# YUSynth-LFO-ioboard.net
KiCad netlist of a schematic drawn in EAGLE
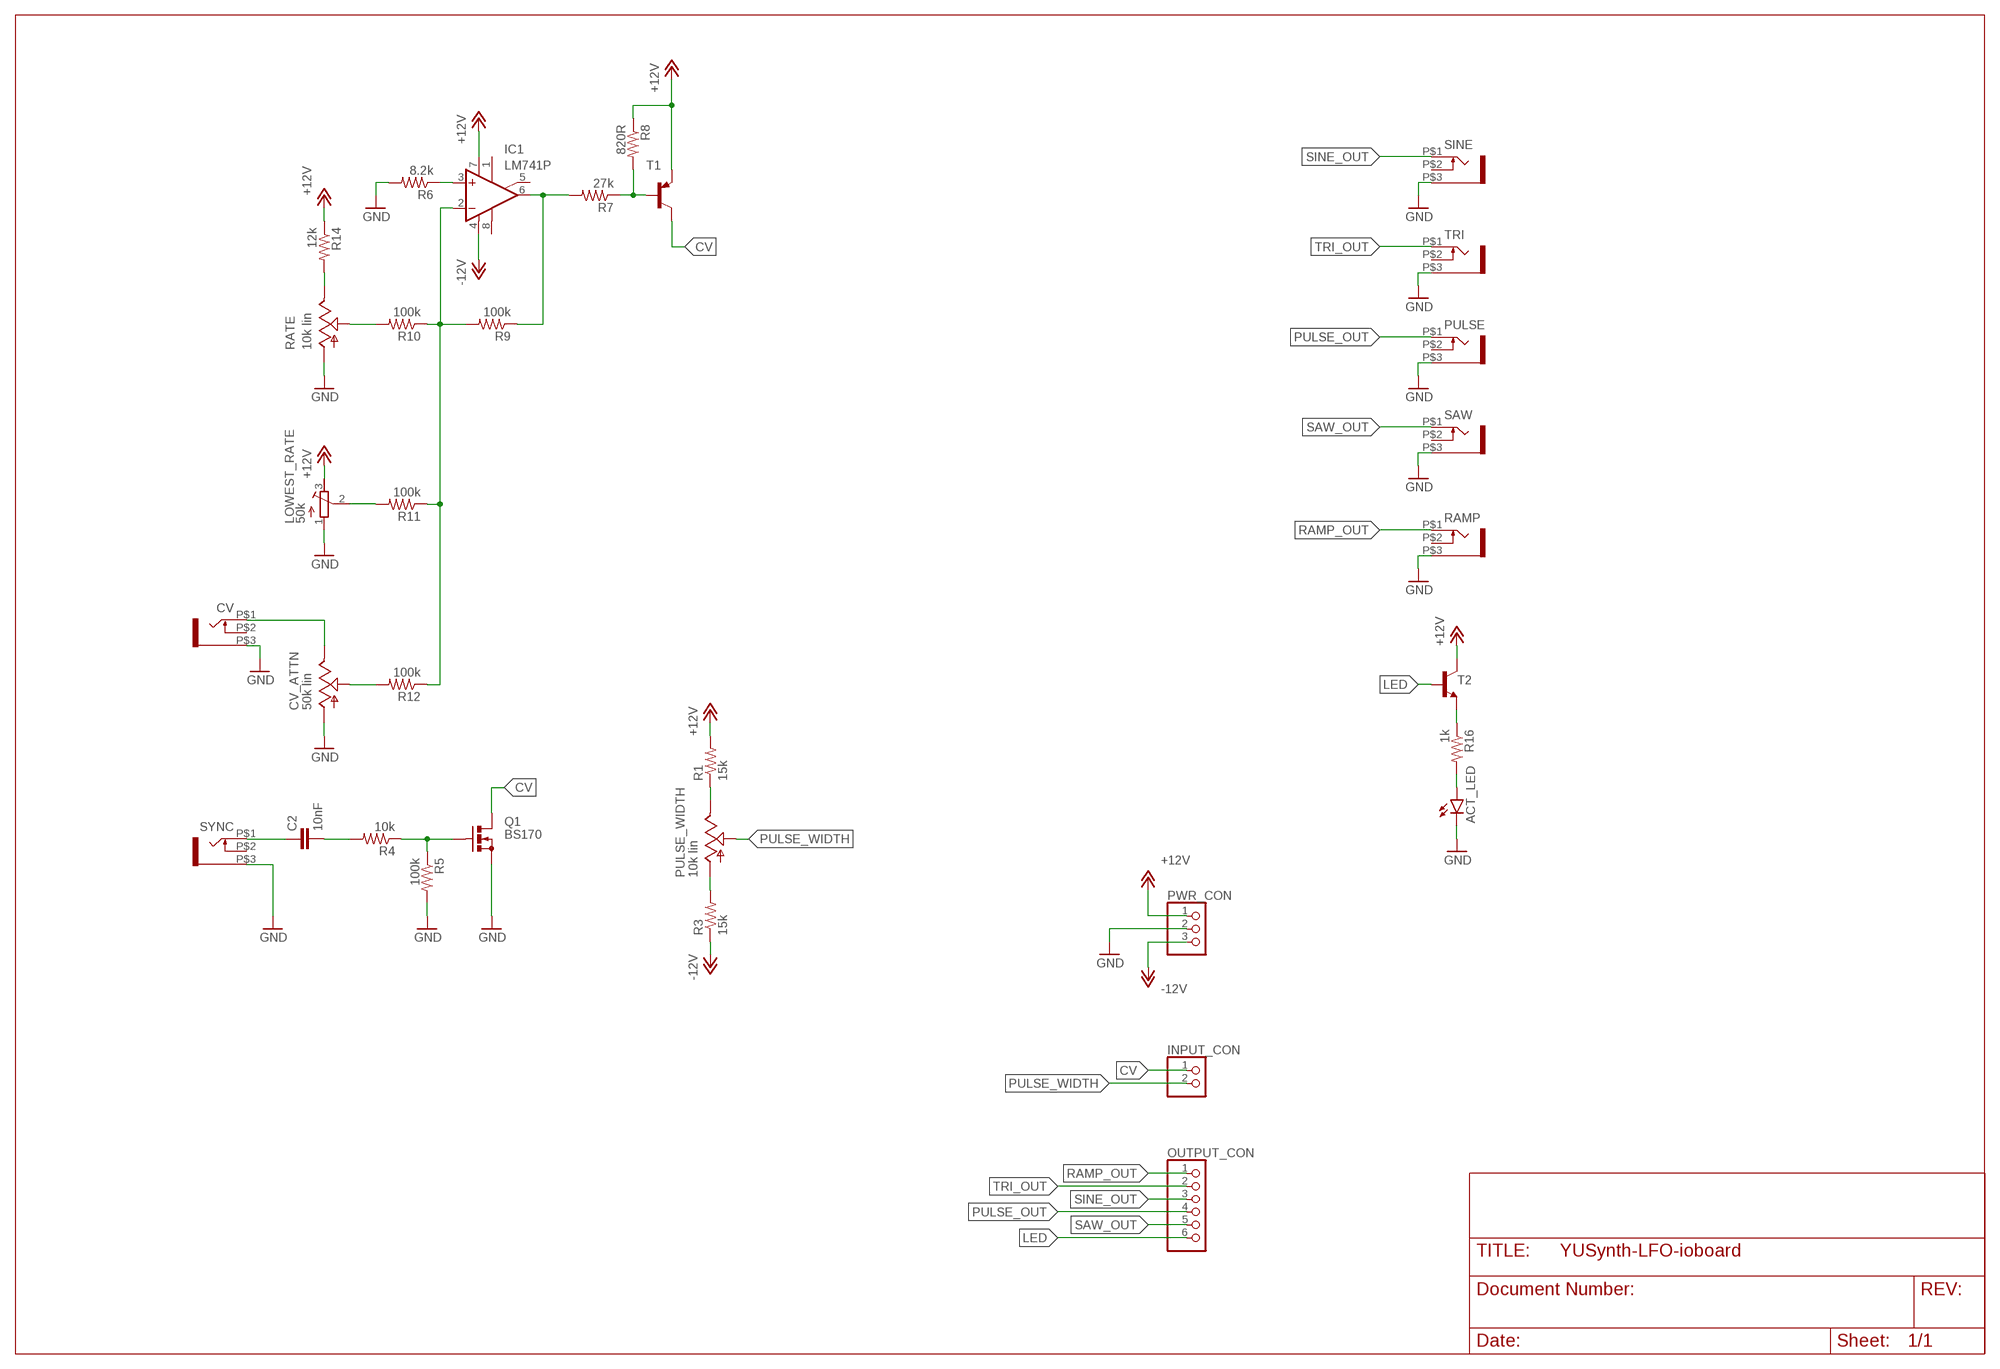
[diagram p0: schematic, sheet 1]

(export (version "E")
  (design (tool "Eeschema 10.0.6"))
  (components
    (comp (ref "ACT_LED")
      (value "LED5MM")
      (footprint "eagle-import:LED5MM")
      (libsource (lib "eagle-import") (part "LED5MM"))
    )
    (comp (ref "C2")
      (value "10nF")
      (footprint "eagle-import:C050-024X044")
      (libsource (lib "eagle-import") (part "C-EU050-024X044"))
    )
    (comp (ref "CV")
      (value "WQP-PJ301M-12_JACK")
      (footprint "eagle-import:WQP-PJ301M-12_JACK")
      (libsource (lib "eagle-import") (part "WQP-PJ301M-12_JACK"))
    )
    (comp (ref "CV_ATTN")
      (value "50k lin")
      (footprint "eagle-import:EVUF")
      (libsource (lib "eagle-import") (part "ALPHA-9MMA"))
    )
    (comp (ref "IC1")
      (value "LM741P")
      (footprint "eagle-import:DIL08")
      (libsource (lib "eagle-import") (part "741PLM"))
    )
    (comp (ref "INPUT_CON")
      (value "PINHD-1X2")
      (footprint "eagle-import:1X02")
      (libsource (lib "eagle-import") (part "PINHD-1X2"))
    )
    (comp (ref "LOWEST_RATE")
      (value "50k")
      (footprint "eagle-import:RTRIM64X")
      (libsource (lib "eagle-import") (part "R-TRIMM64X"))
    )
    (comp (ref "OUTPUT_CON")
      (value "PINHD-1X6")
      (footprint "eagle-import:1X06")
      (libsource (lib "eagle-import") (part "PINHD-1X6"))
    )
    (comp (ref "PULSE")
      (value "WQP-PJ301M-12_JACK")
      (footprint "eagle-import:WQP-PJ301M-12_JACK")
      (libsource (lib "eagle-import") (part "WQP-PJ301M-12_JACK"))
    )
    (comp (ref "PULSE_WIDTH")
      (value "10k lin")
      (footprint "eagle-import:EVUF")
      (libsource (lib "eagle-import") (part "ALPHA-9MMA"))
    )
    (comp (ref "PWR_CON")
      (value "PINHD-1X3")
      (footprint "eagle-import:1X03")
      (libsource (lib "eagle-import") (part "PINHD-1X3"))
    )
    (comp (ref "Q1")
      (value "BS170")
      (footprint "eagle-import:SOT54E")
      (libsource (lib "eagle-import") (part "BS170"))
    )
    (comp (ref "R1")
      (value "15k")
      (footprint "eagle-import:0207_7")
      (libsource (lib "eagle-import") (part "R-US_0207/7"))
    )
    (comp (ref "R3")
      (value "15k")
      (footprint "eagle-import:0207_7")
      (libsource (lib "eagle-import") (part "R-US_0207/7"))
    )
    (comp (ref "R4")
      (value "10k")
      (footprint "eagle-import:0207_7")
      (libsource (lib "eagle-import") (part "R-US_0207/7"))
    )
    (comp (ref "R5")
      (value "100k")
      (footprint "eagle-import:0207_7")
      (libsource (lib "eagle-import") (part "R-US_0207/7"))
    )
    (comp (ref "R6")
      (value "8.2k")
      (footprint "eagle-import:0207_7")
      (libsource (lib "eagle-import") (part "R-US_0207/7"))
    )
    (comp (ref "R7")
      (value "27k")
      (footprint "eagle-import:0207_7")
      (libsource (lib "eagle-import") (part "R-US_0207/7"))
    )
    (comp (ref "R8")
      (value "820R")
      (footprint "eagle-import:0207_7")
      (libsource (lib "eagle-import") (part "R-US_0207/7"))
    )
    (comp (ref "R9")
      (value "100k")
      (footprint "eagle-import:0207_7")
      (libsource (lib "eagle-import") (part "R-US_0207/7"))
    )
    (comp (ref "R10")
      (value "100k")
      (footprint "eagle-import:0207_7")
      (libsource (lib "eagle-import") (part "R-US_0207/7"))
    )
    (comp (ref "R11")
      (value "100k")
      (footprint "eagle-import:0207_7")
      (libsource (lib "eagle-import") (part "R-US_0207/7"))
    )
    (comp (ref "R12")
      (value "100k")
      (footprint "eagle-import:0207_7")
      (libsource (lib "eagle-import") (part "R-US_0207/7"))
    )
    (comp (ref "R14")
      (value "12k")
      (footprint "eagle-import:0207_7")
      (libsource (lib "eagle-import") (part "R-US_0207/7"))
    )
    (comp (ref "R16")
      (value "1k")
      (footprint "eagle-import:0207_7")
      (libsource (lib "eagle-import") (part "R-US_0207/7"))
    )
    (comp (ref "RAMP")
      (value "WQP-PJ301M-12_JACK")
      (footprint "eagle-import:WQP-PJ301M-12_JACK")
      (libsource (lib "eagle-import") (part "WQP-PJ301M-12_JACK"))
    )
    (comp (ref "RATE")
      (value "10k lin")
      (footprint "eagle-import:EVUF")
      (libsource (lib "eagle-import") (part "ALPHA-9MMA"))
    )
    (comp (ref "SAW")
      (value "WQP-PJ301M-12_JACK")
      (footprint "eagle-import:WQP-PJ301M-12_JACK")
      (libsource (lib "eagle-import") (part "WQP-PJ301M-12_JACK"))
    )
    (comp (ref "SINE")
      (value "WQP-PJ301M-12_JACK")
      (footprint "eagle-import:WQP-PJ301M-12_JACK")
      (libsource (lib "eagle-import") (part "WQP-PJ301M-12_JACK"))
    )
    (comp (ref "SYNC")
      (value "WQP-PJ301M-12_JACK")
      (footprint "eagle-import:WQP-PJ301M-12_JACK")
      (libsource (lib "eagle-import") (part "WQP-PJ301M-12_JACK"))
    )
    (comp (ref "T1")
      (value "BC557C-PNP-TO92-EBC")
      (footprint "eagle-import:TO92-EBC")
      (libsource (lib "eagle-import") (part "-PNP-TO92-EBCBC557C"))
    )
    (comp (ref "T2")
      (value "BC547-NPN-TO92-CBE")
      (footprint "eagle-import:TO92-CBE")
      (libsource (lib "eagle-import") (part "-NPN-TO92-CBEBC547"))
    )
    (comp (ref "TRI")
      (value "WQP-PJ301M-12_JACK")
      (footprint "eagle-import:WQP-PJ301M-12_JACK")
      (libsource (lib "eagle-import") (part "WQP-PJ301M-12_JACK"))
    )
  )
  (nets
    (net (code "1") (name "+12V") (class "Default")
      (node (ref "IC1") (pin "7") (pinfunction "V+_7") (pintype "power_in"))
      (node (ref "LOWEST_RATE") (pin "3") (pinfunction "E_3") (pintype "passive"))
      (node (ref "PWR_CON") (pin "1") (pinfunction "1_1") (pintype "passive"))
      (node (ref "R1") (pin "2") (pinfunction "2_2") (pintype "passive"))
      (node (ref "R14") (pin "1") (pinfunction "1_1") (pintype "passive"))
      (node (ref "R8") (pin "1") (pinfunction "1_1") (pintype "passive"))
      (node (ref "T1") (pin "E") (pinfunction "E_E") (pintype "passive"))
      (node (ref "T2") (pin "C") (pinfunction "C_C") (pintype "passive"))
    )
    (net (code "2") (name "-12V") (class "Default")
      (node (ref "IC1") (pin "4") (pinfunction "V-_4") (pintype "power_in"))
      (node (ref "PWR_CON") (pin "3") (pinfunction "3_3") (pintype "passive"))
      (node (ref "R3") (pin "1") (pinfunction "1_1") (pintype "passive"))
    )
    (net (code "3") (name "CV") (class "Default")
      (node (ref "INPUT_CON") (pin "1") (pinfunction "1_1") (pintype "passive"))
      (node (ref "Q1") (pin "D") (pinfunction "D_D") (pintype "passive"))
      (node (ref "T1") (pin "C") (pinfunction "C_C") (pintype "passive"))
    )
    (net (code "4") (name "GND") (class "Default")
      (node (ref "ACT_LED") (pin "K") (pinfunction "C_K") (pintype "passive"))
      (node (ref "CV") (pin "P$3") (pinfunction "1_P$3") (pintype "passive"))
      (node (ref "CV_ATTN") (pin "1") (pinfunction "A_1") (pintype "passive"))
      (node (ref "LOWEST_RATE") (pin "1") (pinfunction "A_1") (pintype "passive"))
      (node (ref "PULSE") (pin "P$3") (pinfunction "1_P$3") (pintype "passive"))
      (node (ref "PWR_CON") (pin "2") (pinfunction "2_2") (pintype "passive"))
      (node (ref "Q1") (pin "S") (pinfunction "S_S") (pintype "passive"))
      (node (ref "R5") (pin "2") (pinfunction "2_2") (pintype "passive"))
      (node (ref "R6") (pin "2") (pinfunction "2_2") (pintype "passive"))
      (node (ref "RAMP") (pin "P$3") (pinfunction "1_P$3") (pintype "passive"))
      (node (ref "RATE") (pin "1") (pinfunction "A_1") (pintype "passive"))
      (node (ref "SAW") (pin "P$3") (pinfunction "1_P$3") (pintype "passive"))
      (node (ref "SINE") (pin "P$3") (pinfunction "1_P$3") (pintype "passive"))
      (node (ref "SYNC") (pin "P$3") (pinfunction "1_P$3") (pintype "passive"))
      (node (ref "TRI") (pin "P$3") (pinfunction "1_P$3") (pintype "passive"))
    )
    (net (code "5") (name "LED") (class "Default")
      (node (ref "OUTPUT_CON") (pin "6") (pinfunction "6_6") (pintype "passive"))
      (node (ref "T2") (pin "B") (pinfunction "B_B") (pintype "passive"))
    )
    (net (code "6") (name "Net-(ACT_LED-PadA)") (class "Default")
      (node (ref "ACT_LED") (pin "A") (pinfunction "A_A") (pintype "passive"))
      (node (ref "R16") (pin "2") (pinfunction "2_2") (pintype "passive"))
    )
    (net (code "7") (name "Net-(C2-Pad2)") (class "Default")
      (node (ref "C2") (pin "2") (pinfunction "2_2") (pintype "passive"))
      (node (ref "R4") (pin "2") (pinfunction "2_2") (pintype "passive"))
    )
    (net (code "8") (name "Net-(CV-2)") (class "Default")
      (node (ref "CV") (pin "P$1") (pinfunction "2_P$1") (pintype "passive"))
      (node (ref "CV_ATTN") (pin "3") (pinfunction "E_3") (pintype "passive"))
    )
    (net (code "9") (name "Net-(CV_ATTN-S)") (class "Default")
      (node (ref "CV_ATTN") (pin "2") (pinfunction "S_2") (pintype "passive"))
      (node (ref "R12") (pin "2") (pinfunction "2_2") (pintype "passive"))
    )
    (net (code "10") (name "Net-(IC1-+IN)") (class "Default")
      (node (ref "IC1") (pin "3") (pinfunction "+IN_3") (pintype "input"))
      (node (ref "R6") (pin "1") (pinfunction "1_1") (pintype "passive"))
    )
    (net (code "11") (name "Net-(IC1--IN)") (class "Default")
      (node (ref "IC1") (pin "2") (pinfunction "-IN_2") (pintype "input"))
      (node (ref "R10") (pin "1") (pinfunction "1_1") (pintype "passive"))
      (node (ref "R11") (pin "1") (pinfunction "1_1") (pintype "passive"))
      (node (ref "R12") (pin "1") (pinfunction "1_1") (pintype "passive"))
      (node (ref "R9") (pin "2") (pinfunction "2_2") (pintype "passive"))
    )
    (net (code "12") (name "Net-(IC1-OUT)") (class "Default")
      (node (ref "IC1") (pin "6") (pinfunction "OUT_6") (pintype "output"))
      (node (ref "R7") (pin "2") (pinfunction "2_2") (pintype "passive"))
      (node (ref "R9") (pin "1") (pinfunction "1_1") (pintype "passive"))
    )
    (net (code "13") (name "Net-(LOWEST_RATE-S)") (class "Default")
      (node (ref "LOWEST_RATE") (pin "2") (pinfunction "S_2") (pintype "passive"))
      (node (ref "R11") (pin "2") (pinfunction "2_2") (pintype "passive"))
    )
    (net (code "14") (name "Net-(PULSE_WIDTH-A)") (class "Default")
      (node (ref "PULSE_WIDTH") (pin "1") (pinfunction "A_1") (pintype "passive"))
      (node (ref "R3") (pin "2") (pinfunction "2_2") (pintype "passive"))
    )
    (net (code "15") (name "Net-(PULSE_WIDTH-E)") (class "Default")
      (node (ref "PULSE_WIDTH") (pin "3") (pinfunction "E_3") (pintype "passive"))
      (node (ref "R1") (pin "1") (pinfunction "1_1") (pintype "passive"))
    )
    (net (code "16") (name "Net-(Q1-PadG)") (class "Default")
      (node (ref "Q1") (pin "G") (pinfunction "G_G") (pintype "passive"))
      (node (ref "R4") (pin "1") (pinfunction "1_1") (pintype "passive"))
      (node (ref "R5") (pin "1") (pinfunction "1_1") (pintype "passive"))
    )
    (net (code "17") (name "Net-(R7-Pad1)") (class "Default")
      (node (ref "R7") (pin "1") (pinfunction "1_1") (pintype "passive"))
      (node (ref "R8") (pin "2") (pinfunction "2_2") (pintype "passive"))
      (node (ref "T1") (pin "B") (pinfunction "B_B") (pintype "passive"))
    )
    (net (code "18") (name "Net-(R16-Pad1)") (class "Default")
      (node (ref "R16") (pin "1") (pinfunction "1_1") (pintype "passive"))
      (node (ref "T2") (pin "E") (pinfunction "E_E") (pintype "passive"))
    )
    (net (code "19") (name "Net-(RATE-E)") (class "Default")
      (node (ref "R14") (pin "2") (pinfunction "2_2") (pintype "passive"))
      (node (ref "RATE") (pin "3") (pinfunction "E_3") (pintype "passive"))
    )
    (net (code "20") (name "Net-(RATE-S)") (class "Default")
      (node (ref "R10") (pin "2") (pinfunction "2_2") (pintype "passive"))
      (node (ref "RATE") (pin "2") (pinfunction "S_2") (pintype "passive"))
    )
    (net (code "21") (name "Net-(SYNC-2)") (class "Default")
      (node (ref "C2") (pin "1") (pinfunction "1_1") (pintype "passive"))
      (node (ref "SYNC") (pin "P$1") (pinfunction "2_P$1") (pintype "passive"))
    )
    (net (code "22") (name "PULSE_OUT") (class "Default")
      (node (ref "OUTPUT_CON") (pin "4") (pinfunction "4_4") (pintype "passive"))
      (node (ref "PULSE") (pin "P$1") (pinfunction "2_P$1") (pintype "passive"))
    )
    (net (code "23") (name "PULSE_WIDTH") (class "Default")
      (node (ref "INPUT_CON") (pin "2") (pinfunction "2_2") (pintype "passive"))
      (node (ref "PULSE_WIDTH") (pin "2") (pinfunction "S_2") (pintype "passive"))
    )
    (net (code "24") (name "RAMP_OUT") (class "Default")
      (node (ref "OUTPUT_CON") (pin "1") (pinfunction "1_1") (pintype "passive"))
      (node (ref "RAMP") (pin "P$1") (pinfunction "2_P$1") (pintype "passive"))
    )
    (net (code "25") (name "SAW_OUT") (class "Default")
      (node (ref "OUTPUT_CON") (pin "5") (pinfunction "5_5") (pintype "passive"))
      (node (ref "SAW") (pin "P$1") (pinfunction "2_P$1") (pintype "passive"))
    )
    (net (code "26") (name "SINE_OUT") (class "Default")
      (node (ref "OUTPUT_CON") (pin "3") (pinfunction "3_3") (pintype "passive"))
      (node (ref "SINE") (pin "P$1") (pinfunction "2_P$1") (pintype "passive"))
    )
    (net (code "27") (name "TRI_OUT") (class "Default")
      (node (ref "OUTPUT_CON") (pin "2") (pinfunction "2_2") (pintype "passive"))
      (node (ref "TRI") (pin "P$1") (pinfunction "2_P$1") (pintype "passive"))
    )
    (net (code "28") (name "unconnected-(CV-3-PadP$2)") (class "Default")
      (node (ref "CV") (pin "P$2") (pinfunction "3_P$2") (pintype "passive"))
    )
    (net (code "29") (name "unconnected-(IC1-ON1-Pad1)") (class "Default")
      (node (ref "IC1") (pin "1") (pinfunction "ON1_1") (pintype "passive"))
    )
    (net (code "30") (name "unconnected-(IC1-ON2-Pad5)") (class "Default")
      (node (ref "IC1") (pin "5") (pinfunction "ON2_5") (pintype "passive"))
    )
    (net (code "31") (name "unconnected-(IC1-OPT-Pad8)") (class "Default")
      (node (ref "IC1") (pin "8") (pinfunction "OPT_8") (pintype "passive"))
    )
    (net (code "32") (name "unconnected-(PULSE-3-PadP$2)") (class "Default")
      (node (ref "PULSE") (pin "P$2") (pinfunction "3_P$2") (pintype "passive"))
    )
    (net (code "33") (name "unconnected-(RAMP-3-PadP$2)") (class "Default")
      (node (ref "RAMP") (pin "P$2") (pinfunction "3_P$2") (pintype "passive"))
    )
    (net (code "34") (name "unconnected-(SAW-3-PadP$2)") (class "Default")
      (node (ref "SAW") (pin "P$2") (pinfunction "3_P$2") (pintype "passive"))
    )
    (net (code "35") (name "unconnected-(SINE-3-PadP$2)") (class "Default")
      (node (ref "SINE") (pin "P$2") (pinfunction "3_P$2") (pintype "passive"))
    )
    (net (code "36") (name "unconnected-(SYNC-3-PadP$2)") (class "Default")
      (node (ref "SYNC") (pin "P$2") (pinfunction "3_P$2") (pintype "passive"))
    )
    (net (code "37") (name "unconnected-(TRI-3-PadP$2)") (class "Default")
      (node (ref "TRI") (pin "P$2") (pinfunction "3_P$2") (pintype "passive"))
    )
  )
)
